# magicmouth-v0_1.net
KiCad netlist of a schematic drawn in EAGLE
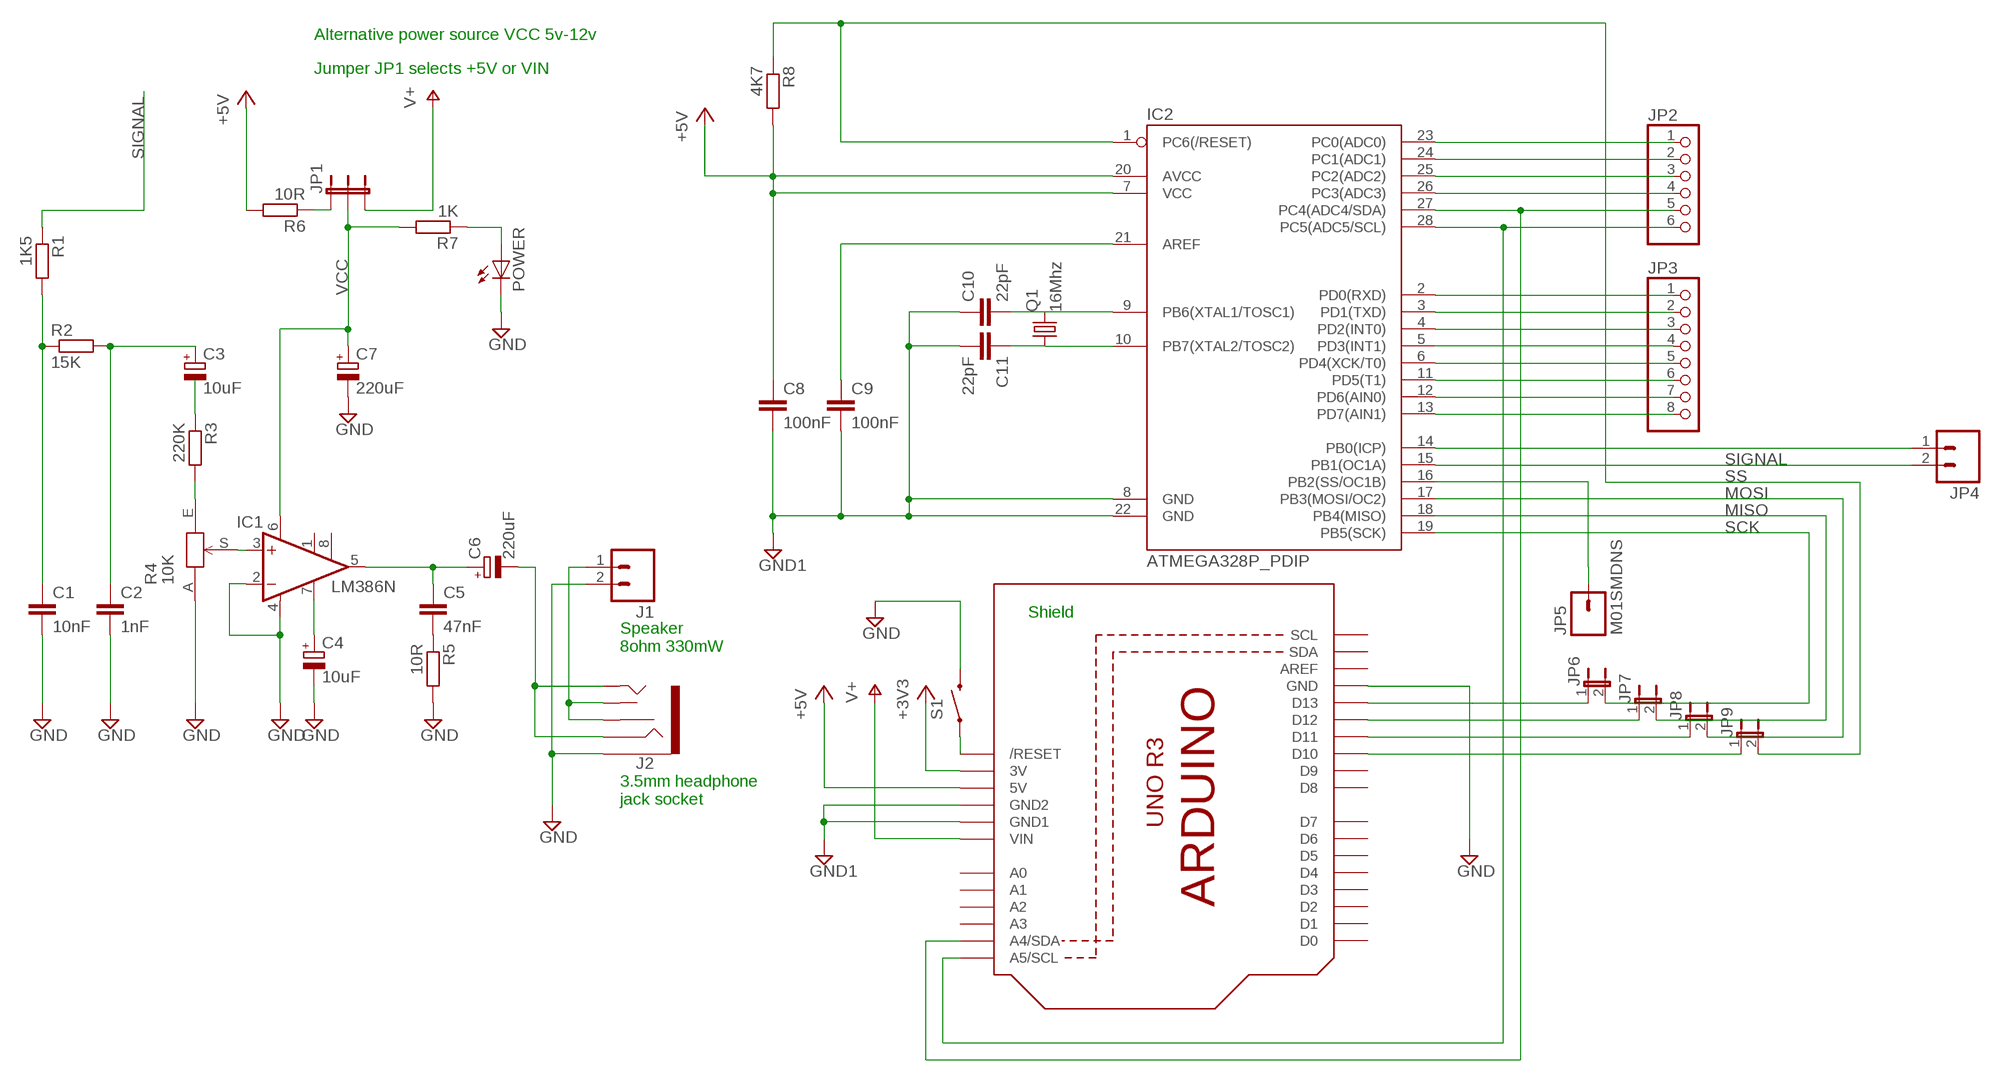
[diagram p0: schematic, sheet 1]

(export (version "E")
  (design (tool "Eeschema 10.0.6"))
  (components
    (comp (ref "C1")
      (value "10nF")
      (footprint "eagle-import:C050-025X075")
      (libsource (lib "eagle-import") (part "resistor_C-EU050-025X075"))
    )
    (comp (ref "C2")
      (value "1nF")
      (footprint "eagle-import:C050-025X075")
      (libsource (lib "eagle-import") (part "resistor_C-EU050-025X075"))
    )
    (comp (ref "C3")
      (value "10uF")
      (footprint "eagle-import:E2,5-7")
      (libsource (lib "eagle-import") (part "CPOL-EUE2.5-7"))
    )
    (comp (ref "C4")
      (value "10uF")
      (footprint "eagle-import:E2,5-7")
      (libsource (lib "eagle-import") (part "CPOL-EUE2.5-7"))
    )
    (comp (ref "C5")
      (value "47nF")
      (footprint "eagle-import:C050-025X075")
      (libsource (lib "eagle-import") (part "resistor_C-EU050-025X075"))
    )
    (comp (ref "C6")
      (value "220uF")
      (footprint "eagle-import:TT5D7L")
      (libsource (lib "eagle-import") (part "CPOL-EUTT5D7L"))
    )
    (comp (ref "C7")
      (value "220uF")
      (footprint "eagle-import:TT5D7L")
      (libsource (lib "eagle-import") (part "CPOL-EUTT5D7L"))
    )
    (comp (ref "C8")
      (value "100nF")
      (footprint "eagle-import:C025-025X050")
      (fields (field (name "CAPACITANCE") "10 nF"))
      (libsource (lib "eagle-import") (part "C-EU025-025X050"))
    )
    (comp (ref "C9")
      (value "100nF")
      (footprint "eagle-import:C025-025X050")
      (fields (field (name "CAPACITANCE") "100 nF"))
      (libsource (lib "eagle-import") (part "C-EU025-025X050"))
    )
    (comp (ref "C10")
      (value "22pF")
      (footprint "eagle-import:C025-025X050")
      (fields (field (name "CAPACITANCE") "22 pf"))
      (libsource (lib "eagle-import") (part "C-EU025-025X050"))
    )
    (comp (ref "C11")
      (value "22pF")
      (footprint "eagle-import:C025-025X050")
      (fields (field (name "CAPACITANCE") "22 pf"))
      (libsource (lib "eagle-import") (part "C-EU025-025X050"))
    )
    (comp (ref "IC1")
      (value "LM386N")
      (footprint "eagle-import:DIL08")
      (libsource (lib "eagle-import") (part "LM386?-N1"))
    )
    (comp (ref "IC2")
      (value "ATMEGA328P_PDIP")
      (footprint "eagle-import:DIL28-3")
      (libsource (lib "eagle-import") (part "ATMEGA328P_PDIP"))
    )
    (comp (ref "J1")
      (value "M023.5MM")
      (footprint "eagle-import:SCREWTERMINAL-3.5MM-2")
      (libsource (lib "eagle-import") (part "M023.5MM"))
    )
    (comp (ref "J2")
      (value "AUDIO-JACK2PTH")
      (footprint "eagle-import:AUDIO-JACK")
      (libsource (lib "eagle-import") (part "AUDIO-JACK2PTH"))
    )
    (comp (ref "JP1")
      (value "JUMPER-3PTH")
      (footprint "eagle-import:1X03")
      (libsource (lib "eagle-import") (part "JUMPER-3PTH"))
    )
    (comp (ref "JP2")
      (value "PINHD-1X6CB")
      (footprint "eagle-import:1X06-CLEANBIG")
      (libsource (lib "eagle-import") (part "PINHD-1X6CB"))
    )
    (comp (ref "JP3")
      (value "PINHD-1X8CLEANBIG")
      (footprint "eagle-import:1X08-CLEANBIG")
      (libsource (lib "eagle-import") (part "PINHD-1X8CLEANBIG"))
    )
    (comp (ref "JP4")
      (value "M021X02_NO_SILK")
      (footprint "eagle-import:1X02_NO_SILK")
      (libsource (lib "eagle-import") (part "M021X02_NO_SILK"))
    )
    (comp (ref "JP5")
      (value "M01SMDNS")
      (footprint "eagle-import:1X01NS")
      (libsource (lib "eagle-import") (part "M01SMDNS"))
    )
    (comp (ref "JP6")
      (value "JUMPER-2PTH")
      (footprint "eagle-import:1X02")
      (libsource (lib "eagle-import") (part "JUMPER-2PTH"))
    )
    (comp (ref "JP7")
      (value "JUMPER-2PTH")
      (footprint "eagle-import:1X02")
      (libsource (lib "eagle-import") (part "JUMPER-2PTH"))
    )
    (comp (ref "JP8")
      (value "JUMPER-2PTH")
      (footprint "eagle-import:1X02")
      (libsource (lib "eagle-import") (part "JUMPER-2PTH"))
    )
    (comp (ref "JP9")
      (value "JUMPER-2PTH")
      (footprint "eagle-import:1X02")
      (libsource (lib "eagle-import") (part "JUMPER-2PTH"))
    )
    (comp (ref "POWER")
      (value "LED3MM")
      (footprint "eagle-import:LED3MM")
      (libsource (lib "eagle-import") (part "LED3MM"))
    )
    (comp (ref "Q1")
      (value "16Mhz")
      (footprint "eagle-import:HC49_S")
      (libsource (lib "eagle-import") (part "CRYSTALHC49S"))
    )
    (comp (ref "R1")
      (value "1K5")
      (footprint "eagle-import:0207_7")
      (libsource (lib "eagle-import") (part "R-EU_0207/7"))
    )
    (comp (ref "R2")
      (value "15K")
      (footprint "eagle-import:0207_7")
      (libsource (lib "eagle-import") (part "R-EU_0207/7"))
    )
    (comp (ref "R3")
      (value "220K")
      (footprint "eagle-import:0207_7")
      (libsource (lib "eagle-import") (part "R-EU_0207/7"))
    )
    (comp (ref "R4")
      (value "10K")
      (footprint "eagle-import:3352T")
      (libsource (lib "eagle-import") (part "TPOT3352"))
    )
    (comp (ref "R5")
      (value "10R")
      (footprint "eagle-import:0207_7")
      (libsource (lib "eagle-import") (part "resistor_R-EU_0207/7"))
    )
    (comp (ref "R6")
      (value "10R")
      (footprint "eagle-import:0207_7")
      (libsource (lib "eagle-import") (part "R-EU_0207/7"))
    )
    (comp (ref "R7")
      (value "1K")
      (footprint "eagle-import:0207_7")
      (libsource (lib "eagle-import") (part "R-EU_0207/7"))
    )
    (comp (ref "R8")
      (value "4K7")
      (footprint "eagle-import:0207_7")
      (fields (field (name "RESISTANCE") "4K7"))
      (libsource (lib "eagle-import") (part "R-EU_0207/7"))
    )
    (comp (ref "S1")
      (value "SWITCH-MOMENTARY-2PTH")
      (footprint "eagle-import:TACTILE-PTH")
      (libsource (lib "eagle-import") (part "SWITCH-MOMENTARY-2PTH"))
    )
    (comp (ref "U1")
      (value "ARDUINOR3-NOIOREF-NOTEXT")
      (footprint "eagle-import:ARDUINOR3-NOTEXT-NOIOREF")
      (libsource (lib "eagle-import") (part "ARDUINOR3-NOIOREF-NOTEXT"))
    )
  )
  (nets
    (net (code "1") (name "+3V3") (class "Default")
      (node (ref "U1") (pin "3V") (pinfunction "3V_3V") (pintype "power_in"))
    )
    (net (code "2") (name "+5V") (class "Default")
      (node (ref "C8") (pin "1") (pinfunction "1_1") (pintype "passive"))
      (node (ref "IC2") (pin "20") (pinfunction "AVCC_20") (pintype "bidirectional"))
      (node (ref "IC2") (pin "7") (pinfunction "VCC_7") (pintype "bidirectional"))
      (node (ref "R6") (pin "2") (pinfunction "2_2") (pintype "passive"))
      (node (ref "R8") (pin "2") (pinfunction "2_2") (pintype "passive"))
      (node (ref "U1") (pin "5V") (pinfunction "5V_5V") (pintype "power_in"))
    )
    (net (code "3") (name "/MISO") (class "Default")
      (node (ref "IC2") (pin "18") (pinfunction "PB4(MISO)_18") (pintype "bidirectional"))
      (node (ref "JP7") (pin "2") (pinfunction "2_2") (pintype "passive"))
    )
    (net (code "4") (name "/MOSI") (class "Default")
      (node (ref "IC2") (pin "17") (pinfunction "PB3(MOSI/OC2)_17") (pintype "bidirectional"))
      (node (ref "JP8") (pin "2") (pinfunction "2_2") (pintype "passive"))
    )
    (net (code "5") (name "/SCK") (class "Default")
      (node (ref "IC2") (pin "19") (pinfunction "PB5(SCK)_19") (pintype "bidirectional"))
      (node (ref "JP6") (pin "2") (pinfunction "2_2") (pintype "passive"))
    )
    (net (code "6") (name "/SIGNAL") (class "Default")
      (node (ref "IC2") (pin "15") (pinfunction "PB1(OC1A)_15") (pintype "bidirectional"))
      (node (ref "JP4") (pin "2") (pinfunction "2_2") (pintype "passive"))
      (node (ref "R1") (pin "1") (pinfunction "1_1") (pintype "passive"))
    )
    (net (code "7") (name "/SS") (class "Default")
      (node (ref "IC2") (pin "1") (pinfunction "PC6(/RESET)_1") (pintype "bidirectional"))
      (node (ref "JP9") (pin "2") (pinfunction "2_2") (pintype "passive"))
      (node (ref "R8") (pin "1") (pinfunction "1_1") (pintype "passive"))
    )
    (net (code "8") (name "/VCC") (class "Default")
      (node (ref "C7") (pin "+") (pinfunction "+_+") (pintype "passive"))
      (node (ref "IC1") (pin "6") (pinfunction "VS_6") (pintype "power_in"))
      (node (ref "JP1") (pin "2") (pinfunction "2_2") (pintype "passive"))
      (node (ref "R7") (pin "2") (pinfunction "2_2") (pintype "passive"))
    )
    (net (code "9") (name "GND") (class "Default")
      (node (ref "C1") (pin "2") (pinfunction "2_2") (pintype "passive"))
      (node (ref "C2") (pin "2") (pinfunction "2_2") (pintype "passive"))
      (node (ref "C4") (pin "-") (pinfunction "-_-") (pintype "passive"))
      (node (ref "C7") (pin "-") (pinfunction "-_-") (pintype "passive"))
      (node (ref "IC1") (pin "2") (pinfunction "-IN_2") (pintype "input"))
      (node (ref "IC1") (pin "4") (pinfunction "GND_4") (pintype "power_in"))
      (node (ref "J1") (pin "2") (pinfunction "2_2") (pintype "passive"))
      (node (ref "J2") (pin "SLEEVE") (pinfunction "SLEEVE_SLEEVE") (pintype "bidirectional"))
      (node (ref "POWER") (pin "K") (pinfunction "C_K") (pintype "passive"))
      (node (ref "R4") (pin "A") (pinfunction "A_A") (pintype "passive"))
      (node (ref "R5") (pin "2") (pinfunction "2_2") (pintype "passive"))
      (node (ref "S1") (pin "3") (pinfunction "2_3") (pintype "passive"))
      (node (ref "U1") (pin "GND") (pinfunction "GND_GND") (pintype "power_in"))
    )
    (net (code "10") (name "GND1") (class "Default")
      (node (ref "C10") (pin "1") (pinfunction "1_1") (pintype "passive"))
      (node (ref "C11") (pin "2") (pinfunction "2_2") (pintype "passive"))
      (node (ref "C8") (pin "2") (pinfunction "2_2") (pintype "passive"))
      (node (ref "C9") (pin "2") (pinfunction "2_2") (pintype "passive"))
      (node (ref "IC2") (pin "22") (pinfunction "GND_22") (pintype "bidirectional"))
      (node (ref "IC2") (pin "8") (pinfunction "GND_8") (pintype "bidirectional"))
      (node (ref "U1") (pin "GND1") (pinfunction "GND1_GND1") (pintype "power_in"))
      (node (ref "U1") (pin "GND2") (pinfunction "GND2_GND2") (pintype "power_in"))
    )
    (net (code "11") (name "Net-(C1-Pad1)") (class "Default")
      (node (ref "C1") (pin "1") (pinfunction "1_1") (pintype "passive"))
      (node (ref "R1") (pin "2") (pinfunction "2_2") (pintype "passive"))
      (node (ref "R2") (pin "1") (pinfunction "1_1") (pintype "passive"))
    )
    (net (code "12") (name "Net-(C2-Pad1)") (class "Default")
      (node (ref "C2") (pin "1") (pinfunction "1_1") (pintype "passive"))
      (node (ref "C3") (pin "+") (pinfunction "+_+") (pintype "passive"))
      (node (ref "R2") (pin "2") (pinfunction "2_2") (pintype "passive"))
    )
    (net (code "13") (name "Net-(C3-Pad-)") (class "Default")
      (node (ref "C3") (pin "-") (pinfunction "-_-") (pintype "passive"))
      (node (ref "R3") (pin "1") (pinfunction "1_1") (pintype "passive"))
    )
    (net (code "14") (name "Net-(C5-Pad2)") (class "Default")
      (node (ref "C5") (pin "2") (pinfunction "2_2") (pintype "passive"))
      (node (ref "R5") (pin "1") (pinfunction "1_1") (pintype "passive"))
    )
    (net (code "15") (name "Net-(C6-Pad-)") (class "Default")
      (node (ref "C6") (pin "-") (pinfunction "-_-") (pintype "passive"))
      (node (ref "J2") (pin "RING") (pinfunction "RING_RING") (pintype "bidirectional"))
      (node (ref "J2") (pin "TIP") (pinfunction "TIP_TIP") (pintype "bidirectional"))
    )
    (net (code "16") (name "Net-(IC1-+IN)") (class "Default")
      (node (ref "IC1") (pin "3") (pinfunction "+IN_3") (pintype "input"))
      (node (ref "R4") (pin "S") (pinfunction "S_S") (pintype "passive"))
    )
    (net (code "17") (name "Net-(IC1-BYPASS)") (class "Default")
      (node (ref "C4") (pin "+") (pinfunction "+_+") (pintype "passive"))
      (node (ref "IC1") (pin "7") (pinfunction "BYPASS_7") (pintype "passive"))
    )
    (net (code "18") (name "Net-(IC1-OUT)") (class "Default")
      (node (ref "C5") (pin "1") (pinfunction "1_1") (pintype "passive"))
      (node (ref "C6") (pin "+") (pinfunction "+_+") (pintype "passive"))
      (node (ref "IC1") (pin "5") (pinfunction "OUT_5") (pintype "output"))
    )
    (net (code "19") (name "Net-(IC2-AREF)") (class "Default")
      (node (ref "C9") (pin "1") (pinfunction "1_1") (pintype "passive"))
      (node (ref "IC2") (pin "21") (pinfunction "AREF_21") (pintype "bidirectional"))
    )
    (net (code "20") (name "Net-(IC2-PB0(ICP))") (class "Default")
      (node (ref "IC2") (pin "14") (pinfunction "PB0(ICP)_14") (pintype "bidirectional"))
      (node (ref "JP4") (pin "1") (pinfunction "1_1") (pintype "passive"))
    )
    (net (code "21") (name "Net-(IC2-PB2(SS{slash}OC1B))") (class "Default")
      (node (ref "IC2") (pin "16") (pinfunction "PB2(SS/OC1B)_16") (pintype "bidirectional"))
      (node (ref "JP5") (pin "1") (pinfunction "1_1") (pintype "passive"))
    )
    (net (code "22") (name "Net-(IC2-PB6(XTAL1{slash}TOSC1))") (class "Default")
      (node (ref "C10") (pin "2") (pinfunction "2_2") (pintype "passive"))
      (node (ref "IC2") (pin "9") (pinfunction "PB6(XTAL1/TOSC1)_9") (pintype "bidirectional"))
      (node (ref "Q1") (pin "2") (pinfunction "2_2") (pintype "passive"))
    )
    (net (code "23") (name "Net-(IC2-PB7(XTAL2{slash}TOSC2))") (class "Default")
      (node (ref "C11") (pin "1") (pinfunction "1_1") (pintype "passive"))
      (node (ref "IC2") (pin "10") (pinfunction "PB7(XTAL2/TOSC2)_10") (pintype "bidirectional"))
      (node (ref "Q1") (pin "1") (pinfunction "1_1") (pintype "passive"))
    )
    (net (code "24") (name "Net-(IC2-PC0(ADC0))") (class "Default")
      (node (ref "IC2") (pin "23") (pinfunction "PC0(ADC0)_23") (pintype "bidirectional"))
      (node (ref "JP2") (pin "1") (pinfunction "1_1") (pintype "passive"))
    )
    (net (code "25") (name "Net-(IC2-PC1(ADC1))") (class "Default")
      (node (ref "IC2") (pin "24") (pinfunction "PC1(ADC1)_24") (pintype "bidirectional"))
      (node (ref "JP2") (pin "2") (pinfunction "2_2") (pintype "passive"))
    )
    (net (code "26") (name "Net-(IC2-PC2(ADC2))") (class "Default")
      (node (ref "IC2") (pin "25") (pinfunction "PC2(ADC2)_25") (pintype "bidirectional"))
      (node (ref "JP2") (pin "3") (pinfunction "3_3") (pintype "passive"))
    )
    (net (code "27") (name "Net-(IC2-PC3(ADC3))") (class "Default")
      (node (ref "IC2") (pin "26") (pinfunction "PC3(ADC3)_26") (pintype "bidirectional"))
      (node (ref "JP2") (pin "4") (pinfunction "4_4") (pintype "passive"))
    )
    (net (code "28") (name "Net-(IC2-PC4(ADC4{slash}SDA))") (class "Default")
      (node (ref "IC2") (pin "27") (pinfunction "PC4(ADC4/SDA)_27") (pintype "bidirectional"))
      (node (ref "JP2") (pin "5") (pinfunction "5_5") (pintype "passive"))
      (node (ref "U1") (pin "A4") (pinfunction "A4/SDA_A4") (pintype "bidirectional"))
    )
    (net (code "29") (name "Net-(IC2-PC5(ADC5{slash}SCL))") (class "Default")
      (node (ref "IC2") (pin "28") (pinfunction "PC5(ADC5/SCL)_28") (pintype "bidirectional"))
      (node (ref "JP2") (pin "6") (pinfunction "6_6") (pintype "passive"))
      (node (ref "U1") (pin "A5") (pinfunction "A5/SCL_A5") (pintype "bidirectional"))
    )
    (net (code "30") (name "Net-(IC2-PD0(RXD))") (class "Default")
      (node (ref "IC2") (pin "2") (pinfunction "PD0(RXD)_2") (pintype "bidirectional"))
      (node (ref "JP3") (pin "1") (pinfunction "1_1") (pintype "passive"))
    )
    (net (code "31") (name "Net-(IC2-PD1(TXD))") (class "Default")
      (node (ref "IC2") (pin "3") (pinfunction "PD1(TXD)_3") (pintype "bidirectional"))
      (node (ref "JP3") (pin "2") (pinfunction "2_2") (pintype "passive"))
    )
    (net (code "32") (name "Net-(IC2-PD2(INT0))") (class "Default")
      (node (ref "IC2") (pin "4") (pinfunction "PD2(INT0)_4") (pintype "bidirectional"))
      (node (ref "JP3") (pin "3") (pinfunction "3_3") (pintype "passive"))
    )
    (net (code "33") (name "Net-(IC2-PD3(INT1))") (class "Default")
      (node (ref "IC2") (pin "5") (pinfunction "PD3(INT1)_5") (pintype "bidirectional"))
      (node (ref "JP3") (pin "4") (pinfunction "4_4") (pintype "passive"))
    )
    (net (code "34") (name "Net-(IC2-PD4(XCK{slash}T0))") (class "Default")
      (node (ref "IC2") (pin "6") (pinfunction "PD4(XCK/T0)_6") (pintype "bidirectional"))
      (node (ref "JP3") (pin "5") (pinfunction "5_5") (pintype "passive"))
    )
    (net (code "35") (name "Net-(IC2-PD5(T1))") (class "Default")
      (node (ref "IC2") (pin "11") (pinfunction "PD5(T1)_11") (pintype "bidirectional"))
      (node (ref "JP3") (pin "6") (pinfunction "6_6") (pintype "passive"))
    )
    (net (code "36") (name "Net-(IC2-PD6(AIN0))") (class "Default")
      (node (ref "IC2") (pin "12") (pinfunction "PD6(AIN0)_12") (pintype "bidirectional"))
      (node (ref "JP3") (pin "7") (pinfunction "7_7") (pintype "passive"))
    )
    (net (code "37") (name "Net-(IC2-PD7(AIN1))") (class "Default")
      (node (ref "IC2") (pin "13") (pinfunction "PD7(AIN1)_13") (pintype "bidirectional"))
      (node (ref "JP3") (pin "8") (pinfunction "8_8") (pintype "passive"))
    )
    (net (code "38") (name "Net-(J1-Pad1)") (class "Default")
      (node (ref "J1") (pin "1") (pinfunction "1_1") (pintype "passive"))
      (node (ref "J2") (pin "RSH") (pinfunction "RSH_RSH") (pintype "bidirectional"))
      (node (ref "J2") (pin "TSH") (pinfunction "TSH_TSH") (pintype "bidirectional"))
    )
    (net (code "39") (name "Net-(JP1-Pad1)") (class "Default")
      (node (ref "JP1") (pin "1") (pinfunction "1_1") (pintype "passive"))
      (node (ref "R6") (pin "1") (pinfunction "1_1") (pintype "passive"))
    )
    (net (code "40") (name "Net-(JP6-Pad1)") (class "Default")
      (node (ref "JP6") (pin "1") (pinfunction "1_1") (pintype "passive"))
      (node (ref "U1") (pin "D13") (pinfunction "D13_D13") (pintype "bidirectional"))
    )
    (net (code "41") (name "Net-(JP7-Pad1)") (class "Default")
      (node (ref "JP7") (pin "1") (pinfunction "1_1") (pintype "passive"))
      (node (ref "U1") (pin "D12") (pinfunction "D12_D12") (pintype "bidirectional"))
    )
    (net (code "42") (name "Net-(JP8-Pad1)") (class "Default")
      (node (ref "JP8") (pin "1") (pinfunction "1_1") (pintype "passive"))
      (node (ref "U1") (pin "D11") (pinfunction "D11_D11") (pintype "bidirectional"))
    )
    (net (code "43") (name "Net-(JP9-Pad1)") (class "Default")
      (node (ref "JP9") (pin "1") (pinfunction "1_1") (pintype "passive"))
      (node (ref "U1") (pin "D10") (pinfunction "D10_D10") (pintype "bidirectional"))
    )
    (net (code "44") (name "Net-(POWER-PadA)") (class "Default")
      (node (ref "POWER") (pin "A") (pinfunction "A_A") (pintype "passive"))
      (node (ref "R7") (pin "1") (pinfunction "1_1") (pintype "passive"))
    )
    (net (code "45") (name "Net-(R3-Pad2)") (class "Default")
      (node (ref "R3") (pin "2") (pinfunction "2_2") (pintype "passive"))
      (node (ref "R4") (pin "E") (pinfunction "E_E") (pintype "passive"))
    )
    (net (code "46") (name "Net-(U1-{slash}RESET)") (class "Default")
      (node (ref "S1") (pin "1") (pinfunction "1_1") (pintype "passive"))
      (node (ref "U1") (pin "RESET") (pinfunction "/RESET_RESET") (pintype "bidirectional"))
    )
    (net (code "47") (name "V+") (class "Default")
      (node (ref "JP1") (pin "3") (pinfunction "3_3") (pintype "passive"))
      (node (ref "U1") (pin "VIN") (pinfunction "VIN_VIN") (pintype "power_in"))
    )
    (net (code "48") (name "unconnected-(IC1-GAIN-Pad1)") (class "Default")
      (node (ref "IC1") (pin "1") (pinfunction "GAIN_1") (pintype "passive"))
    )
    (net (code "49") (name "unconnected-(IC1-GAIN-Pad8)") (class "Default")
      (node (ref "IC1") (pin "8") (pinfunction "GAIN_8") (pintype "passive"))
    )
    (net (code "50") (name "unconnected-(U1-PadA0)") (class "Default")
      (node (ref "U1") (pin "A0") (pinfunction "A0_A0") (pintype "bidirectional"))
    )
    (net (code "51") (name "unconnected-(U1-PadA1)") (class "Default")
      (node (ref "U1") (pin "A1") (pinfunction "A1_A1") (pintype "bidirectional"))
    )
    (net (code "52") (name "unconnected-(U1-PadA2)") (class "Default")
      (node (ref "U1") (pin "A2") (pinfunction "A2_A2") (pintype "bidirectional"))
    )
    (net (code "53") (name "unconnected-(U1-PadA3)") (class "Default")
      (node (ref "U1") (pin "A3") (pinfunction "A3_A3") (pintype "bidirectional"))
    )
    (net (code "54") (name "unconnected-(U1-PadAREF)") (class "Default")
      (node (ref "U1") (pin "AREF") (pinfunction "AREF_AREF") (pintype "bidirectional"))
    )
    (net (code "55") (name "unconnected-(U1-PadD0)") (class "Default")
      (node (ref "U1") (pin "D0") (pinfunction "D0_D0") (pintype "bidirectional"))
    )
    (net (code "56") (name "unconnected-(U1-PadD1)") (class "Default")
      (node (ref "U1") (pin "D1") (pinfunction "D1_D1") (pintype "bidirectional"))
    )
    (net (code "57") (name "unconnected-(U1-PadD2)") (class "Default")
      (node (ref "U1") (pin "D2") (pinfunction "D2_D2") (pintype "bidirectional"))
    )
    (net (code "58") (name "unconnected-(U1-PadD3)") (class "Default")
      (node (ref "U1") (pin "D3") (pinfunction "D3_D3") (pintype "bidirectional"))
    )
    (net (code "59") (name "unconnected-(U1-PadD4)") (class "Default")
      (node (ref "U1") (pin "D4") (pinfunction "D4_D4") (pintype "bidirectional"))
    )
    (net (code "60") (name "unconnected-(U1-PadD5)") (class "Default")
      (node (ref "U1") (pin "D5") (pinfunction "D5_D5") (pintype "bidirectional"))
    )
    (net (code "61") (name "unconnected-(U1-PadD6)") (class "Default")
      (node (ref "U1") (pin "D6") (pinfunction "D6_D6") (pintype "bidirectional"))
    )
    (net (code "62") (name "unconnected-(U1-PadD7)") (class "Default")
      (node (ref "U1") (pin "D7") (pinfunction "D7_D7") (pintype "bidirectional"))
    )
    (net (code "63") (name "unconnected-(U1-PadD8)") (class "Default")
      (node (ref "U1") (pin "D8") (pinfunction "D8_D8") (pintype "bidirectional"))
    )
    (net (code "64") (name "unconnected-(U1-PadD9)") (class "Default")
      (node (ref "U1") (pin "D9") (pinfunction "D9_D9") (pintype "bidirectional"))
    )
    (net (code "65") (name "unconnected-(U1-PadSCL)") (class "Default")
      (node (ref "U1") (pin "SCL") (pinfunction "SCL_SCL") (pintype "bidirectional"))
    )
    (net (code "66") (name "unconnected-(U1-PadSDA)") (class "Default")
      (node (ref "U1") (pin "SDA") (pinfunction "SDA_SDA") (pintype "bidirectional"))
    )
  )
)
